# Main.net
KiCad netlist of a schematic drawn in Altium Designer
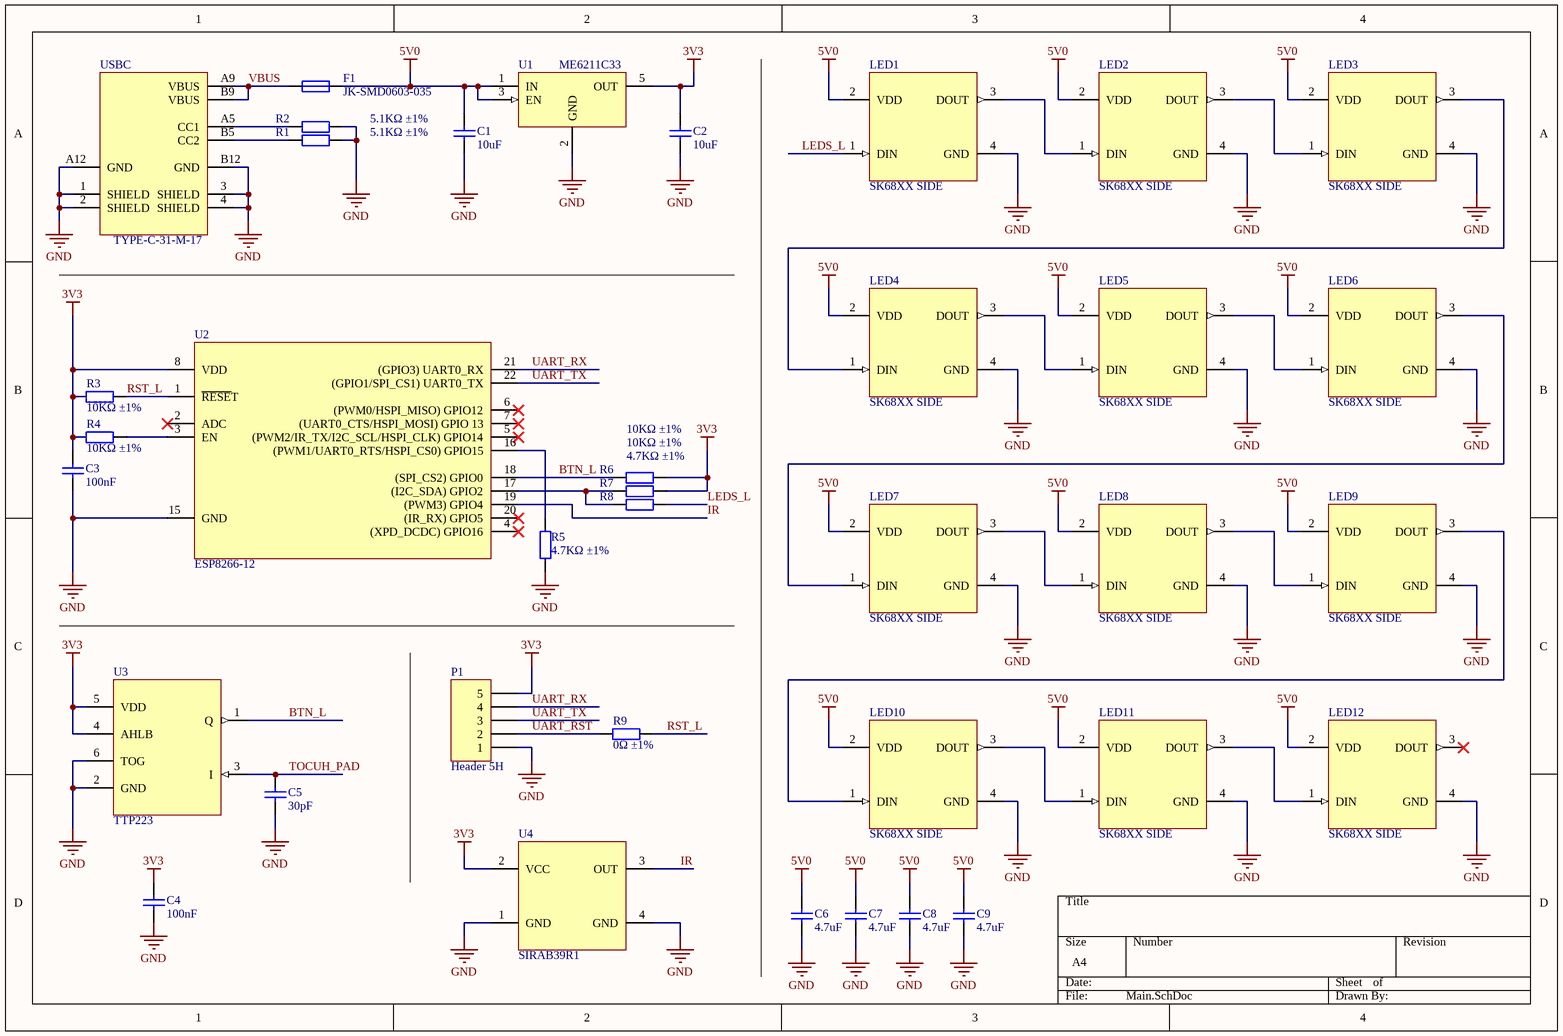
[diagram p0: Main.SchDoc]

(export (version "E")
  (design (tool "Eeschema 10.0.6"))
  (components
    (comp (ref "C1")
      (value "10uF")
      (footprint "0603_C")
      (description "Chip capacitors")
      (fields
        (field (name "MANUFACTURER") "Samsung Electro-Mechanics")
        (field (name "PARTNUMBER") "CL10A106KP8NNNC")
      )
      (libsource (lib "Miscellaneous Devices LC") (part "0603 10uF (106) 10% 10V"))
    )
    (comp (ref "C2")
      (value "10uF")
      (footprint "0603_C")
      (description "Chip capacitors")
      (fields
        (field (name "MANUFACTURER") "Samsung Electro-Mechanics")
        (field (name "PARTNUMBER") "CL10A106KP8NNNC")
      )
      (libsource (lib "Miscellaneous Devices LC") (part "0603 10uF (106) 10% 10V"))
    )
    (comp (ref "C3")
      (value "100nF")
      (footprint "0603_C")
      (description "Chip capacitors")
      (fields (field (name "MANUFACTURER") "YAGEO") (field (name "PARTNUMBER") "CC0603KRX7R9BB104"))
      (libsource (lib "Miscellaneous Devices LC") (part "0603 100nF (104) 10% 50V"))
    )
    (comp (ref "C4")
      (value "100nF")
      (footprint "0603_C")
      (description "Chip capacitors")
      (fields (field (name "MANUFACTURER") "YAGEO") (field (name "PARTNUMBER") "CC0603KRX7R9BB104"))
      (libsource (lib "Miscellaneous Devices LC") (part "0603 100nF (104) 10% 50V"))
    )
    (comp (ref "C5")
      (value "30pF")
      (footprint "0603_C")
      (description "Chip capacitors")
      (fields
        (field (name "MANUFACTURER") "Samsung Electro-Mechanics")
        (field (name "PARTNUMBER") "CL10C300JB8NNNC")
      )
      (libsource (lib "Miscellaneous Devices LC") (part "0603 30pF (300) 5% 50V"))
    )
    (comp (ref "C6")
      (value "4.7uF")
      (footprint "0603_C")
      (description "Chip capacitors")
      (fields
        (field (name "MANUFACTURER") "Samsung Electro-Mechanics")
        (field (name "PARTNUMBER") "CL10A475KO8NNNC")
      )
      (libsource (lib "Miscellaneous Devices LC") (part "0603 4.7uF (475) 10% 16V"))
    )
    (comp (ref "C7")
      (value "4.7uF")
      (footprint "0603_C")
      (description "Chip capacitors")
      (fields
        (field (name "MANUFACTURER") "Samsung Electro-Mechanics")
        (field (name "PARTNUMBER") "CL10A475KO8NNNC")
      )
      (libsource (lib "Miscellaneous Devices LC") (part "0603 4.7uF (475) 10% 16V"))
    )
    (comp (ref "C8")
      (value "4.7uF")
      (footprint "0603_C")
      (description "Chip capacitors")
      (fields
        (field (name "MANUFACTURER") "Samsung Electro-Mechanics")
        (field (name "PARTNUMBER") "CL10A475KO8NNNC")
      )
      (libsource (lib "Miscellaneous Devices LC") (part "0603 4.7uF (475) 10% 16V"))
    )
    (comp (ref "C9")
      (value "4.7uF")
      (footprint "0603_C")
      (description "Chip capacitors")
      (fields
        (field (name "MANUFACTURER") "Samsung Electro-Mechanics")
        (field (name "PARTNUMBER") "CL10A475KO8NNNC")
      )
      (libsource (lib "Miscellaneous Devices LC") (part "0603 4.7uF (475) 10% 16V"))
    )
    (comp (ref "F1")
      (value "JK-SMD0603-035")
      (footprint "0603")
      (description "PTC Resettable Fuse")
      (fields (field (name "MANUFACTURER") "Jinrui Electronic Materials Co."))
      (libsource (lib "SchLib") (part "JK-SMD0603-035"))
    )
    (comp (ref "LED1")
      (value "SK68XX SIDE")
      (footprint "SK68XX-SIDE")
      (description "Addressable LED")
      (fields
        (field (name "MANUFACTURER") "Shenzhen Normand Electronic Co.,Ltd")
        (field (name "PARTNUMBER") "SK6812 SIDE")
      )
      (libsource (lib "SchLib") (part "SK6805-SIDE"))
    )
    (comp (ref "LED2")
      (value "SK68XX SIDE")
      (footprint "SK68XX-SIDE")
      (description "Addressable LED")
      (fields
        (field (name "MANUFACTURER") "Shenzhen Normand Electronic Co.,Ltd")
        (field (name "PARTNUMBER") "SK6812 SIDE")
      )
      (libsource (lib "SchLib") (part "SK6805-SIDE"))
    )
    (comp (ref "LED3")
      (value "SK68XX SIDE")
      (footprint "SK68XX-SIDE")
      (description "Addressable LED")
      (fields
        (field (name "MANUFACTURER") "Shenzhen Normand Electronic Co.,Ltd")
        (field (name "PARTNUMBER") "SK6812 SIDE")
      )
      (libsource (lib "SchLib") (part "SK6805-SIDE"))
    )
    (comp (ref "LED4")
      (value "SK68XX SIDE")
      (footprint "SK68XX-SIDE")
      (description "Addressable LED")
      (fields
        (field (name "MANUFACTURER") "Shenzhen Normand Electronic Co.,Ltd")
        (field (name "PARTNUMBER") "SK6812 SIDE")
      )
      (libsource (lib "SchLib") (part "SK6805-SIDE"))
    )
    (comp (ref "LED5")
      (value "SK68XX SIDE")
      (footprint "SK68XX-SIDE")
      (description "Addressable LED")
      (fields
        (field (name "MANUFACTURER") "Shenzhen Normand Electronic Co.,Ltd")
        (field (name "PARTNUMBER") "SK6812 SIDE")
      )
      (libsource (lib "SchLib") (part "SK6805-SIDE"))
    )
    (comp (ref "LED6")
      (value "SK68XX SIDE")
      (footprint "SK68XX-SIDE")
      (description "Addressable LED")
      (fields
        (field (name "MANUFACTURER") "Shenzhen Normand Electronic Co.,Ltd")
        (field (name "PARTNUMBER") "SK6812 SIDE")
      )
      (libsource (lib "SchLib") (part "SK6805-SIDE"))
    )
    (comp (ref "LED7")
      (value "SK68XX SIDE")
      (footprint "SK68XX-SIDE")
      (description "Addressable LED")
      (fields
        (field (name "MANUFACTURER") "Shenzhen Normand Electronic Co.,Ltd")
        (field (name "PARTNUMBER") "SK6812 SIDE")
      )
      (libsource (lib "SchLib") (part "SK6805-SIDE"))
    )
    (comp (ref "LED8")
      (value "SK68XX SIDE")
      (footprint "SK68XX-SIDE")
      (description "Addressable LED")
      (fields
        (field (name "MANUFACTURER") "Shenzhen Normand Electronic Co.,Ltd")
        (field (name "PARTNUMBER") "SK6812 SIDE")
      )
      (libsource (lib "SchLib") (part "SK6805-SIDE"))
    )
    (comp (ref "LED9")
      (value "SK68XX SIDE")
      (footprint "SK68XX-SIDE")
      (description "Addressable LED")
      (fields
        (field (name "MANUFACTURER") "Shenzhen Normand Electronic Co.,Ltd")
        (field (name "PARTNUMBER") "SK6812 SIDE")
      )
      (libsource (lib "SchLib") (part "SK6805-SIDE"))
    )
    (comp (ref "LED10")
      (value "SK68XX SIDE")
      (footprint "SK68XX-SIDE")
      (description "Addressable LED")
      (fields
        (field (name "MANUFACTURER") "Shenzhen Normand Electronic Co.,Ltd")
        (field (name "PARTNUMBER") "SK6812 SIDE")
      )
      (libsource (lib "SchLib") (part "SK6805-SIDE"))
    )
    (comp (ref "LED11")
      (value "SK68XX SIDE")
      (footprint "SK68XX-SIDE")
      (description "Addressable LED")
      (fields
        (field (name "MANUFACTURER") "Shenzhen Normand Electronic Co.,Ltd")
        (field (name "PARTNUMBER") "SK6812 SIDE")
      )
      (libsource (lib "SchLib") (part "SK6805-SIDE"))
    )
    (comp (ref "LED12")
      (value "SK68XX SIDE")
      (footprint "SK68XX-SIDE")
      (description "Addressable LED")
      (fields
        (field (name "MANUFACTURER") "Shenzhen Normand Electronic Co.,Ltd")
        (field (name "PARTNUMBER") "SK6812 SIDE")
      )
      (libsource (lib "SchLib") (part "SK6805-SIDE"))
    )
    (comp (ref "P1")
      (value "Header 5H")
      (footprint "HDR1X5H")
      (description "Header, 5-Pin, Right Angle")
      (fields (field (name "PUBLISHER") "Altium Limited"))
      (libsource (lib "Miscellaneous Connectors") (part "Header 5H"))
    )
    (comp (ref "R1")
      (value "5.1KΩ ±1%")
      (footprint "0603_R")
      (description "Chip resistor")
      (fields (field (name "MANUFACTURER") "Uniroyal Elec") (field (name "PARTNUMBER") "0603WAF5101T5E"))
      (libsource (lib "Miscellaneous Devices LC") (part "0603 5.1K (5101) 1%"))
    )
    (comp (ref "R2")
      (value "5.1KΩ ±1%")
      (footprint "0603_R")
      (description "Chip resistor")
      (fields (field (name "MANUFACTURER") "Uniroyal Elec") (field (name "PARTNUMBER") "0603WAF5101T5E"))
      (libsource (lib "Miscellaneous Devices LC") (part "0603 5.1K (5101) 1%"))
    )
    (comp (ref "R3")
      (value "10KΩ ±1%")
      (footprint "0603_R")
      (description "Chip resistor")
      (fields (field (name "MANUFACTURER") "Uniroyal Elec") (field (name "PARTNUMBER") "0603WAF1002T5E"))
      (libsource (lib "Miscellaneous Devices LC") (part "0603 10K (1002) 1%"))
    )
    (comp (ref "R4")
      (value "10KΩ ±1%")
      (footprint "0603_R")
      (description "Chip resistor")
      (fields (field (name "MANUFACTURER") "Uniroyal Elec") (field (name "PARTNUMBER") "0603WAF1002T5E"))
      (libsource (lib "Miscellaneous Devices LC") (part "0603 10K (1002) 1%"))
    )
    (comp (ref "R5")
      (value "4.7KΩ ±1%")
      (footprint "0603_R")
      (description "Chip resistor")
      (fields (field (name "MANUFACTURER") "Uniroyal Elec") (field (name "PARTNUMBER") "0603WAF4701T5E"))
      (libsource (lib "") (part "0603 4.7K (4701) 1%_1"))
    )
    (comp (ref "R6")
      (value "10KΩ ±1%")
      (footprint "0603_R")
      (description "Chip resistor")
      (fields (field (name "MANUFACTURER") "Uniroyal Elec") (field (name "PARTNUMBER") "0603WAF1002T5E"))
      (libsource (lib "") (part "0603 10K (1002) 1%_1"))
    )
    (comp (ref "R7")
      (value "10KΩ ±1%")
      (footprint "0603_R")
      (description "Chip resistor")
      (fields (field (name "MANUFACTURER") "Uniroyal Elec") (field (name "PARTNUMBER") "0603WAF1002T5E"))
      (libsource (lib "Miscellaneous Devices LC") (part "0603 10K (1002) 1%"))
    )
    (comp (ref "R8")
      (value "4.7KΩ ±1%")
      (footprint "0603_R")
      (description "Chip resistor")
      (fields (field (name "MANUFACTURER") "Uniroyal Elec") (field (name "PARTNUMBER") "0603WAF4701T5E"))
      (libsource (lib "Miscellaneous Devices LC") (part "0603 4.7K (4701) 1%"))
    )
    (comp (ref "R9")
      (value "0Ω ±1%")
      (footprint "0603_R")
      (description "Chip resistor")
      (fields (field (name "MANUFACTURER") "Uniroyal Elec") (field (name "PARTNUMBER") "0603WAF0000T5E"))
      (libsource (lib "Miscellaneous Devices LC") (part "0603 0R (0R0) 1%"))
    )
    (comp (ref "U1")
      (value "ME6211C33")
      (footprint "SOT-23-5")
      (description "LDO")
      (fields
        (field (name "MANUFACTURER") "MICRONE(Nanjing Micro One Elec)")
        (field (name "PARTNUMBER") "ME6211C33M5G-N")
      )
      (libsource (lib "SchLib") (part "ME6211C33"))
    )
    (comp (ref "U2")
      (value "ESP8266-12")
      (footprint "ESP-12E")
      (libsource (lib "SchLib") (part "ESP8266-12"))
    )
    (comp (ref "U3")
      (value "TTP223")
      (footprint "SOT-23-6")
      (description "Touch Pad Detector IC")
      (fields (field (name "MANUFACTURER") "Tontek Design Tech") (field (name "PARTNUMBER") "TTP223N-HA6"))
      (libsource (lib "SchLib") (part "TTP223"))
    )
    (comp (ref "U4")
      (value "SIRAB39R1")
      (footprint "SMD_SIRAB39R1")
      (description "Infrared remote receiver")
      (fields (field (name "MANUFACTURER") "Hangzhou Silan Microelectronics"))
      (libsource (lib "SchLib") (part "SIRAB39R1"))
    )
    (comp (ref "USBC")
      (value "TYPE-C-31-M-17")
      (footprint "USBC")
      (description "USB Connectors")
      (fields (field (name "MANUFACTURER") "Korean Hroparts Elec"))
      (libsource (lib "SchLib") (part "TYPE-C-31-M-17"))
    )
  )
  (nets
    (net (code "1") (name "/BTN_L") (class "Default")
      (node (ref "R6") (pin "2") (pinfunction "2_2") (pintype "passive"))
      (node (ref "U2") (pin "18") (pinfunction "(SPI_CS2)_GPIO0_18") (pintype "passive"))
      (node (ref "U3") (pin "1") (pinfunction "Q_1") (pintype "output"))
    )
    (net (code "2") (name "/IR") (class "Default")
      (node (ref "U2") (pin "19") (pinfunction "(PWM3)_GPIO4_19") (pintype "passive"))
      (node (ref "U4") (pin "3") (pinfunction "OUT_3") (pintype "passive"))
    )
    (net (code "3") (name "/LEDS_L") (class "Default")
      (node (ref "LED1") (pin "1") (pinfunction "DIN_1") (pintype "input"))
      (node (ref "R8") (pin "2") (pinfunction "2_2") (pintype "passive"))
    )
    (net (code "4") (name "/RST_L") (class "Default")
      (node (ref "R3") (pin "2") (pinfunction "2_2") (pintype "passive"))
      (node (ref "R9") (pin "2") (pinfunction "2_2") (pintype "passive"))
      (node (ref "U2") (pin "1") (pinfunction "~{RESE}T_1") (pintype "passive"))
    )
    (net (code "5") (name "/TOCUH_PAD") (class "Default")
      (node (ref "C5") (pin "2") (pinfunction "2_2") (pintype "passive"))
      (node (ref "U3") (pin "3") (pinfunction "I_3") (pintype "input"))
    )
    (net (code "6") (name "/UART_RST") (class "Default")
      (node (ref "P1") (pin "2") (pinfunction "2_2") (pintype "passive"))
      (node (ref "R9") (pin "1") (pinfunction "1_1") (pintype "passive"))
    )
    (net (code "7") (name "/UART_RX") (class "Default")
      (node (ref "P1") (pin "4") (pinfunction "4_4") (pintype "passive"))
      (node (ref "U2") (pin "21") (pinfunction "(GPIO3)_UART0_RX_21") (pintype "passive"))
    )
    (net (code "8") (name "/UART_TX") (class "Default")
      (node (ref "P1") (pin "3") (pinfunction "3_3") (pintype "passive"))
      (node (ref "U2") (pin "22") (pinfunction "(GPIO1/SPI_CS1)_UART0_TX_22") (pintype "passive"))
    )
    (net (code "9") (name "/VBUS") (class "Default")
      (node (ref "F1") (pin "1") (pinfunction "1_1") (pintype "passive"))
      (node (ref "USBC") (pin "A9") (pinfunction "VBUS_A9") (pintype "passive"))
      (node (ref "USBC") (pin "B9") (pinfunction "VBUS_B9") (pintype "passive"))
    )
    (net (code "10") (name "3V3") (class "Default")
      (node (ref "C2") (pin "2") (pinfunction "2_2") (pintype "passive"))
      (node (ref "C3") (pin "2") (pinfunction "2_2") (pintype "passive"))
      (node (ref "C4") (pin "2") (pinfunction "2_2") (pintype "passive"))
      (node (ref "P1") (pin "5") (pinfunction "5_5") (pintype "passive"))
      (node (ref "R3") (pin "1") (pinfunction "1_1") (pintype "passive"))
      (node (ref "R4") (pin "1") (pinfunction "1_1") (pintype "passive"))
      (node (ref "R6") (pin "1") (pinfunction "1_1") (pintype "passive"))
      (node (ref "R7") (pin "2") (pinfunction "2_2") (pintype "passive"))
      (node (ref "U1") (pin "5") (pinfunction "OUT_5") (pintype "power_in"))
      (node (ref "U2") (pin "8") (pinfunction "VDD_8") (pintype "passive"))
      (node (ref "U3") (pin "4") (pinfunction "AHLB_4") (pintype "passive"))
      (node (ref "U3") (pin "5") (pinfunction "VDD_5") (pintype "power_in"))
      (node (ref "U4") (pin "2") (pinfunction "VCC_2") (pintype "passive"))
    )
    (net (code "11") (name "5V0") (class "Default")
      (node (ref "C1") (pin "2") (pinfunction "2_2") (pintype "passive"))
      (node (ref "C6") (pin "2") (pinfunction "2_2") (pintype "passive"))
      (node (ref "C7") (pin "2") (pinfunction "2_2") (pintype "passive"))
      (node (ref "C8") (pin "2") (pinfunction "2_2") (pintype "passive"))
      (node (ref "C9") (pin "2") (pinfunction "2_2") (pintype "passive"))
      (node (ref "F1") (pin "2") (pinfunction "2_2") (pintype "passive"))
      (node (ref "LED1") (pin "2") (pinfunction "VDD_2") (pintype "power_in"))
      (node (ref "LED10") (pin "2") (pinfunction "VDD_2") (pintype "power_in"))
      (node (ref "LED11") (pin "2") (pinfunction "VDD_2") (pintype "power_in"))
      (node (ref "LED12") (pin "2") (pinfunction "VDD_2") (pintype "power_in"))
      (node (ref "LED2") (pin "2") (pinfunction "VDD_2") (pintype "power_in"))
      (node (ref "LED3") (pin "2") (pinfunction "VDD_2") (pintype "power_in"))
      (node (ref "LED4") (pin "2") (pinfunction "VDD_2") (pintype "power_in"))
      (node (ref "LED5") (pin "2") (pinfunction "VDD_2") (pintype "power_in"))
      (node (ref "LED6") (pin "2") (pinfunction "VDD_2") (pintype "power_in"))
      (node (ref "LED7") (pin "2") (pinfunction "VDD_2") (pintype "power_in"))
      (node (ref "LED8") (pin "2") (pinfunction "VDD_2") (pintype "power_in"))
      (node (ref "LED9") (pin "2") (pinfunction "VDD_2") (pintype "power_in"))
      (node (ref "U1") (pin "1") (pinfunction "IN_1") (pintype "power_in"))
      (node (ref "U1") (pin "3") (pinfunction "EN_3") (pintype "input"))
    )
    (net (code "12") (name "GND") (class "Default")
      (node (ref "C1") (pin "1") (pinfunction "1_1") (pintype "passive"))
      (node (ref "C2") (pin "1") (pinfunction "1_1") (pintype "passive"))
      (node (ref "C3") (pin "1") (pinfunction "1_1") (pintype "passive"))
      (node (ref "C4") (pin "1") (pinfunction "1_1") (pintype "passive"))
      (node (ref "C5") (pin "1") (pinfunction "1_1") (pintype "passive"))
      (node (ref "C6") (pin "1") (pinfunction "1_1") (pintype "passive"))
      (node (ref "C7") (pin "1") (pinfunction "1_1") (pintype "passive"))
      (node (ref "C8") (pin "1") (pinfunction "1_1") (pintype "passive"))
      (node (ref "C9") (pin "1") (pinfunction "1_1") (pintype "passive"))
      (node (ref "LED1") (pin "4") (pinfunction "GND_4") (pintype "power_in"))
      (node (ref "LED10") (pin "4") (pinfunction "GND_4") (pintype "power_in"))
      (node (ref "LED11") (pin "4") (pinfunction "GND_4") (pintype "power_in"))
      (node (ref "LED12") (pin "4") (pinfunction "GND_4") (pintype "power_in"))
      (node (ref "LED2") (pin "4") (pinfunction "GND_4") (pintype "power_in"))
      (node (ref "LED3") (pin "4") (pinfunction "GND_4") (pintype "power_in"))
      (node (ref "LED4") (pin "4") (pinfunction "GND_4") (pintype "power_in"))
      (node (ref "LED5") (pin "4") (pinfunction "GND_4") (pintype "power_in"))
      (node (ref "LED6") (pin "4") (pinfunction "GND_4") (pintype "power_in"))
      (node (ref "LED7") (pin "4") (pinfunction "GND_4") (pintype "power_in"))
      (node (ref "LED8") (pin "4") (pinfunction "GND_4") (pintype "power_in"))
      (node (ref "LED9") (pin "4") (pinfunction "GND_4") (pintype "power_in"))
      (node (ref "P1") (pin "1") (pinfunction "1_1") (pintype "passive"))
      (node (ref "R1") (pin "1") (pinfunction "1_1") (pintype "passive"))
      (node (ref "R2") (pin "1") (pinfunction "1_1") (pintype "passive"))
      (node (ref "R5") (pin "1") (pinfunction "1_1") (pintype "passive"))
      (node (ref "U1") (pin "2") (pinfunction "GND_2") (pintype "power_in"))
      (node (ref "U2") (pin "15") (pinfunction "GND_15") (pintype "passive"))
      (node (ref "U3") (pin "2") (pinfunction "GND_2") (pintype "power_in"))
      (node (ref "U3") (pin "6") (pinfunction "TOG_6") (pintype "passive"))
      (node (ref "U4") (pin "1") (pinfunction "GND_1") (pintype "passive"))
      (node (ref "U4") (pin "4") (pinfunction "GND_4") (pintype "passive"))
      (node (ref "USBC") (pin "1") (pinfunction "SHIELD_1") (pintype "passive"))
      (node (ref "USBC") (pin "2") (pinfunction "SHIELD_2") (pintype "passive"))
      (node (ref "USBC") (pin "3") (pinfunction "SHIELD_3") (pintype "passive"))
      (node (ref "USBC") (pin "4") (pinfunction "SHIELD_4") (pintype "passive"))
      (node (ref "USBC") (pin "A12") (pinfunction "GND_A12") (pintype "passive"))
      (node (ref "USBC") (pin "B12") (pinfunction "GND_B12") (pintype "passive"))
    )
    (net (code "13") (name "Net-(LED1-DOUT)") (class "Default")
      (node (ref "LED1") (pin "3") (pinfunction "DOUT_3") (pintype "output"))
      (node (ref "LED2") (pin "1") (pinfunction "DIN_1") (pintype "input"))
    )
    (net (code "14") (name "Net-(LED2-DOUT)") (class "Default")
      (node (ref "LED2") (pin "3") (pinfunction "DOUT_3") (pintype "output"))
      (node (ref "LED3") (pin "1") (pinfunction "DIN_1") (pintype "input"))
    )
    (net (code "15") (name "Net-(LED3-DOUT)") (class "Default")
      (node (ref "LED3") (pin "3") (pinfunction "DOUT_3") (pintype "output"))
      (node (ref "LED4") (pin "1") (pinfunction "DIN_1") (pintype "input"))
    )
    (net (code "16") (name "Net-(LED4-DOUT)") (class "Default")
      (node (ref "LED4") (pin "3") (pinfunction "DOUT_3") (pintype "output"))
      (node (ref "LED5") (pin "1") (pinfunction "DIN_1") (pintype "input"))
    )
    (net (code "17") (name "Net-(LED5-DOUT)") (class "Default")
      (node (ref "LED5") (pin "3") (pinfunction "DOUT_3") (pintype "output"))
      (node (ref "LED6") (pin "1") (pinfunction "DIN_1") (pintype "input"))
    )
    (net (code "18") (name "Net-(LED6-DOUT)") (class "Default")
      (node (ref "LED6") (pin "3") (pinfunction "DOUT_3") (pintype "output"))
      (node (ref "LED7") (pin "1") (pinfunction "DIN_1") (pintype "input"))
    )
    (net (code "19") (name "Net-(LED7-DOUT)") (class "Default")
      (node (ref "LED7") (pin "3") (pinfunction "DOUT_3") (pintype "output"))
      (node (ref "LED8") (pin "1") (pinfunction "DIN_1") (pintype "input"))
    )
    (net (code "20") (name "Net-(LED8-DOUT)") (class "Default")
      (node (ref "LED8") (pin "3") (pinfunction "DOUT_3") (pintype "output"))
      (node (ref "LED9") (pin "1") (pinfunction "DIN_1") (pintype "input"))
    )
    (net (code "21") (name "Net-(LED10-DIN)") (class "Default")
      (node (ref "LED10") (pin "1") (pinfunction "DIN_1") (pintype "input"))
      (node (ref "LED9") (pin "3") (pinfunction "DOUT_3") (pintype "output"))
    )
    (net (code "22") (name "Net-(LED10-DOUT)") (class "Default")
      (node (ref "LED10") (pin "3") (pinfunction "DOUT_3") (pintype "output"))
      (node (ref "LED11") (pin "1") (pinfunction "DIN_1") (pintype "input"))
    )
    (net (code "23") (name "Net-(LED11-DOUT)") (class "Default")
      (node (ref "LED11") (pin "3") (pinfunction "DOUT_3") (pintype "output"))
      (node (ref "LED12") (pin "1") (pinfunction "DIN_1") (pintype "input"))
    )
    (net (code "24") (name "Net-(U2-(I2C_SDA)_GPIO2)") (class "Default")
      (node (ref "R7") (pin "1") (pinfunction "1_1") (pintype "passive"))
      (node (ref "R8") (pin "1") (pinfunction "1_1") (pintype "passive"))
      (node (ref "U2") (pin "17") (pinfunction "(I2C_SDA)_GPIO2_17") (pintype "passive"))
    )
    (net (code "25") (name "Net-(U2-(PWM1{slash}UART0_RTS{slash}HSPI_CS0)_GPIO15)") (class "Default")
      (node (ref "R5") (pin "2") (pinfunction "2_2") (pintype "passive"))
      (node (ref "U2") (pin "16") (pinfunction "(PWM1/UART0_RTS/HSPI_CS0)_GPIO15_16") (pintype "passive"))
    )
    (net (code "26") (name "Net-(U2-EN)") (class "Default")
      (node (ref "R4") (pin "2") (pinfunction "2_2") (pintype "passive"))
      (node (ref "U2") (pin "3") (pinfunction "EN_3") (pintype "passive"))
    )
    (net (code "27") (name "Net-(USBC-CC1)") (class "Default")
      (node (ref "R2") (pin "2") (pinfunction "2_2") (pintype "passive"))
      (node (ref "USBC") (pin "A5") (pinfunction "CC1_A5") (pintype "passive"))
    )
    (net (code "28") (name "Net-(USBC-CC2)") (class "Default")
      (node (ref "R1") (pin "2") (pinfunction "2_2") (pintype "passive"))
      (node (ref "USBC") (pin "B5") (pinfunction "CC2_B5") (pintype "passive"))
    )
    (net (code "29") (name "unconnected-(LED12-DOUT-Pad3)") (class "Default")
      (node (ref "LED12") (pin "3") (pinfunction "DOUT_3") (pintype "output+no_connect"))
    )
    (net (code "30") (name "unconnected-(U2-(IR_RX)_GPIO5-Pad20)") (class "Default")
      (node (ref "U2") (pin "20") (pinfunction "(IR_RX)_GPIO5_20") (pintype "passive+no_connect"))
    )
    (net (code "31") (name "unconnected-(U2-(PWM0{slash}HSPI_MISO)_GPIO12-Pad6)") (class "Default")
      (node (ref "U2") (pin "6") (pinfunction "(PWM0/HSPI_MISO)_GPIO12_6") (pintype "passive+no_connect"))
    )
    (net (code "32") (name "unconnected-(U2-(PWM2{slash}IR_TX{slash}I2C_SCL{slash}HSPI_CLK)_GPIO14-Pad5)") (class "Default")
      (node (ref "U2") (pin "5") (pinfunction "(PWM2/IR_TX/I2C_SCL/HSPI_CLK)_GPIO14_5") (pintype "passive+no_connect"))
    )
    (net (code "33") (name "unconnected-(U2-(UART0_CTS{slash}HSPI_MOSI)_GPIO_13-Pad7)") (class "Default")
      (node (ref "U2") (pin "7") (pinfunction "(UART0_CTS/HSPI_MOSI)_GPIO_13_7") (pintype "passive+no_connect"))
    )
    (net (code "34") (name "unconnected-(U2-(XPD_DCDC)_GPIO16-Pad4)") (class "Default")
      (node (ref "U2") (pin "4") (pinfunction "(XPD_DCDC)_GPIO16_4") (pintype "passive+no_connect"))
    )
    (net (code "35") (name "unconnected-(U2-ADC-Pad2)") (class "Default")
      (node (ref "U2") (pin "2") (pinfunction "ADC_2") (pintype "passive+no_connect"))
    )
  )
)
